# PowerSource.net
KiCad netlist of a schematic drawn in Altium Designer
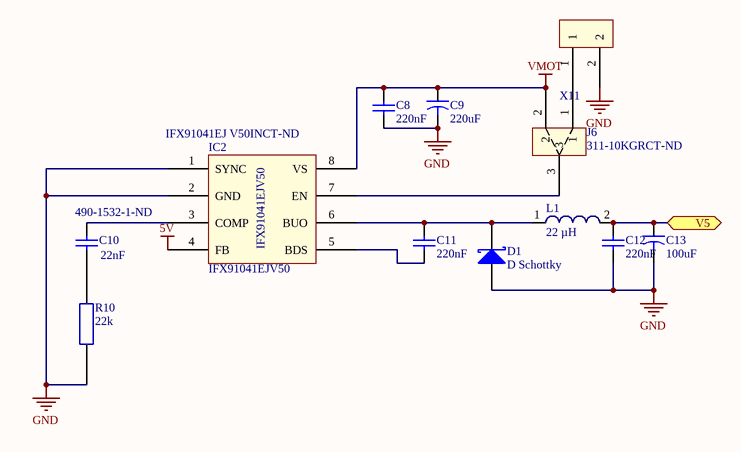
[diagram p0: PowerSource.SchDoc]

(export (version "E")
  (design (tool "Eeschema 10.0.6"))
  (components
    (comp (ref "C8")
      (value "220nF")
      (footprint "Res 0603")
      (description "Capacitor")
      (fields (field (name "Comment") "Cap") (field (name "PUBLISHER") "Altium Limited"))
      (libsource (lib "Miscellaneous Devices") (part "Cap"))
    )
    (comp (ref "C9")
      (value "220uF")
      (footprint "CAPR5-4X5")
      (description "Capacitor")
      (fields (field (name "Comment") "Cap2") (field (name "PUBLISHER") "Altium Limited"))
      (libsource (lib "Miscellaneous Devices") (part "Cap2"))
    )
    (comp (ref "C10")
      (value "22nF")
      (footprint "Res 0603")
      (description "Capacitor")
      (fields
        (field (name "SUPPLIER PART NUMBER 1") "490-1532-1-ND")
        (field (name "Comment") "Cap")
        (field (name "PUBLISHER") "Altium Limited")
      )
      (libsource (lib "Miscellaneous Devices") (part "Cap"))
    )
    (comp (ref "C11")
      (value "220nF")
      (footprint "Res 0603")
      (description "Capacitor")
      (fields (field (name "Comment") "Cap") (field (name "PUBLISHER") "Altium Limited"))
      (libsource (lib "Miscellaneous Devices") (part "Cap"))
    )
    (comp (ref "C12")
      (value "220nF")
      (footprint "Res 0603")
      (description "Capacitor")
      (fields (field (name "Comment") "Cap") (field (name "PUBLISHER") "Altium Limited"))
      (libsource (lib "Miscellaneous Devices") (part "Cap"))
    )
    (comp (ref "C13")
      (value "100uF")
      (footprint "CAPR5-4X5")
      (description "Capacitor")
      (fields (field (name "Comment") "Cap2") (field (name "PUBLISHER") "Altium Limited"))
      (libsource (lib "Miscellaneous Devices") (part "Cap2"))
    )
    (comp (ref "D1")
      (value "D Schottky")
      (footprint "SMB")
      (description "Schottky Diode")
      (fields (field (name "PUBLISHER") "Altium Limited"))
      (libsource (lib "Miscellaneous Devices") (part "D Schottky"))
    )
    (comp (ref "IC2")
      (value "IFX91041EJV50")
      (footprint "IFX91041EJV50")
      (fields (field (name "SUPPLIER PART NUMBER 1") "IFX91041EJ V50INCT-ND"))
      (libsource (lib "Schlib") (part "IFX91041EJV50"))
    )
    (comp (ref "J6")
      (value "VCC to GND Jumper")
      (footprint "VCC to GND Jumper")
      (fields (field (name "SUPPLIER PART NUMBER 1") "311-10KGRCT-ND"))
      (libsource (lib "Schlib") (part "VCC to GND Jumper"))
    )
    (comp (ref "L1")
      (value "22 µH")
      (footprint "WE-PD 7345 Plastic Base")
      (description "SMD-Shielded Power Inductor WE-PD, L=22 µH")
      (fields
        (field (name "PARTNO") "7447779122")
        (field (name "MANUFACTURER") "Würth Elektronik eiSos GmbH")
        (field (name "CREATED BY") "Christin Zierenner")
      )
      (libsource (lib "WE-PD") (part "WE-PD 7345, M Plastic Base, 7447779122"))
    )
    (comp (ref "R10") (value "22k") (footprint "Res 0603") (libsource (lib "Schlib") (part "Res")))
    (comp (ref "X11")
      (value "2p Connector")
      (footprint "2p 2.54 pitch")
      (libsource (lib "Schlib") (part "2p Connector"))
    )
  )
  (nets
    (net (code "1") (name "/V5") (class "Default")
      (node (ref "C12") (pin "2") (pinfunction "2_2") (pintype "passive"))
      (node (ref "C13") (pin "1") (pinfunction "1_1") (pintype "passive"))
      (node (ref "L1") (pin "2") (pinfunction "2_2") (pintype "passive"))
    )
    (net (code "2") (name "5V") (class "Default")
      (node (ref "IC2") (pin "4") (pinfunction "FB_4") (pintype "passive"))
    )
    (net (code "3") (name "GND") (class "Default")
      (node (ref "C12") (pin "1") (pinfunction "1_1") (pintype "passive"))
      (node (ref "C13") (pin "2") (pinfunction "2_2") (pintype "passive"))
      (node (ref "C8") (pin "1") (pinfunction "1_1") (pintype "passive"))
      (node (ref "C9") (pin "2") (pinfunction "2_2") (pintype "passive"))
      (node (ref "D1") (pin "1") (pinfunction "A_1") (pintype "passive"))
      (node (ref "IC2") (pin "1") (pinfunction "SYNC_1") (pintype "passive"))
      (node (ref "IC2") (pin "2") (pinfunction "GND_2") (pintype "passive"))
      (node (ref "R10") (pin "1") (pinfunction "1_1") (pintype "passive"))
      (node (ref "X11") (pin "2") (pinfunction "2_2") (pintype "passive"))
    )
    (net (code "4") (name "Net-(C10-Pad1)") (class "Default")
      (node (ref "C10") (pin "1") (pinfunction "1_1") (pintype "passive"))
      (node (ref "R10") (pin "2") (pinfunction "2_2") (pintype "passive"))
    )
    (net (code "5") (name "Net-(D1-K)") (class "Default")
      (node (ref "C11") (pin "2") (pinfunction "2_2") (pintype "passive"))
      (node (ref "D1") (pin "2") (pinfunction "K_2") (pintype "passive"))
      (node (ref "IC2") (pin "6") (pinfunction "BUO_6") (pintype "passive"))
      (node (ref "L1") (pin "1") (pinfunction "1_1") (pintype "passive"))
    )
    (net (code "6") (name "Net-(IC2-BDS)") (class "Default")
      (node (ref "C11") (pin "1") (pinfunction "1_1") (pintype "passive"))
      (node (ref "IC2") (pin "5") (pinfunction "BDS_5") (pintype "passive"))
    )
    (net (code "7") (name "Net-(IC2-COMP)") (class "Default")
      (node (ref "C10") (pin "2") (pinfunction "2_2") (pintype "passive"))
      (node (ref "IC2") (pin "3") (pinfunction "COMP_3") (pintype "passive"))
    )
    (net (code "8") (name "Net-(IC2-EN)") (class "Default")
      (node (ref "IC2") (pin "7") (pinfunction "EN_7") (pintype "passive"))
      (node (ref "J6") (pin "3") (pinfunction "3_3") (pintype "passive"))
    )
    (net (code "9") (name "Net-(J6-Pad1)") (class "Default")
      (node (ref "J6") (pin "1") (pinfunction "1_1") (pintype "passive"))
      (node (ref "X11") (pin "1") (pinfunction "1_1") (pintype "passive"))
    )
    (net (code "10") (name "VMOT") (class "Default")
      (node (ref "C8") (pin "2") (pinfunction "2_2") (pintype "passive"))
      (node (ref "C9") (pin "1") (pinfunction "1_1") (pintype "passive"))
      (node (ref "IC2") (pin "8") (pinfunction "VS_8") (pintype "passive"))
      (node (ref "J6") (pin "2") (pinfunction "2_2") (pintype "passive"))
    )
  )
)
